# RC_simple.net
KiCad netlist of a schematic drawn in EAGLE
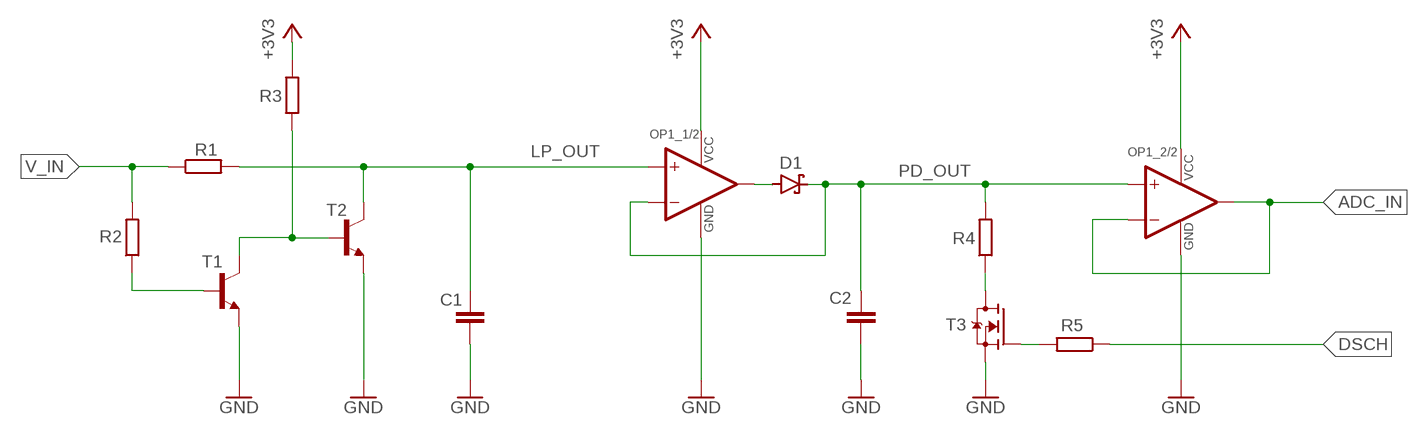
[diagram p0: schematic, sheet 1]

(export (version "E")
  (design (tool "Eeschema 10.0.6"))
  (components
    (comp (ref "C1")
      (value "CAP_CERAMIC_0603")
      (footprint "eagle-import:SMD_0603C")
      (libsource (lib "eagle-import") (part "CAP_CERAMIC_0603"))
    )
    (comp (ref "C2")
      (value "CAP_CERAMIC_0603")
      (footprint "eagle-import:SMD_0603C")
      (libsource (lib "eagle-import") (part "CAP_CERAMIC_0603"))
    )
    (comp (ref "D1")
      (value "BAT54")
      (footprint "eagle-import:SOT23")
      (libsource (lib "eagle-import") (part "BAT54"))
    )
    (comp (ref "OP1")
      (value "MAX_OP_AMPUMAX")
      (footprint "eagle-import:SOT23-8")
      (libsource (lib "eagle-import") (part "MAX_OP_AMPUMAX"))
    )
    (comp (ref "OP2")
      (value "MAX_OP_AMPUMAX")
      (footprint "eagle-import:SOT23-8")
      (libsource (lib "eagle-import") (part "MAX_OP_AMPUMAX"))
    )
    (comp (ref "R1")
      (value "RESISTOR_0603")
      (footprint "eagle-import:SMD_0603")
      (libsource (lib "eagle-import") (part "RESISTOR_0603"))
    )
    (comp (ref "R2")
      (value "RESISTOR_0603")
      (footprint "eagle-import:SMD_0603")
      (libsource (lib "eagle-import") (part "RESISTOR_0603"))
    )
    (comp (ref "R3")
      (value "RESISTOR_0603")
      (footprint "eagle-import:SMD_0603")
      (libsource (lib "eagle-import") (part "RESISTOR_0603"))
    )
    (comp (ref "R4")
      (value "RESISTOR_0603")
      (footprint "eagle-import:SMD_0603")
      (libsource (lib "eagle-import") (part "RESISTOR_0603"))
    )
    (comp (ref "R5")
      (value "RESISTOR_0603")
      (footprint "eagle-import:SMD_0603")
      (libsource (lib "eagle-import") (part "RESISTOR_0603"))
    )
    (comp (ref "T1")
      (value "BC847")
      (footprint "eagle-import:SOT23")
      (libsource (lib "eagle-import") (part "BC847"))
    )
    (comp (ref "T2")
      (value "BC847")
      (footprint "eagle-import:SOT23")
      (libsource (lib "eagle-import") (part "BC847"))
    )
    (comp (ref "T3")
      (value "BSS138")
      (footprint "eagle-import:SOT-23-3")
      (libsource (lib "eagle-import") (part "BSS138"))
    )
  )
  (nets
    (net (code "1") (name "+3V3") (class "Default")
      (node (ref "OP1") (pin "P$8") (pinfunction "V+_P$8") (pintype "power_in"))
      (node (ref "OP2") (pin "P$8") (pinfunction "V+_P$8") (pintype "power_in"))
      (node (ref "R3") (pin "2") (pinfunction "2_2") (pintype "passive"))
    )
    (net (code "2") (name "/LP_OUT") (class "Default")
      (node (ref "C1") (pin "1") (pinfunction "1_1") (pintype "passive"))
      (node (ref "OP1") (pin "P$3") (pinfunction "+IN_P$3") (pintype "input"))
      (node (ref "R1") (pin "2") (pinfunction "2_2") (pintype "passive"))
      (node (ref "T2") (pin "3") (pinfunction "C_3") (pintype "passive"))
    )
    (net (code "3") (name "/PD_OUT") (class "Default")
      (node (ref "C2") (pin "1") (pinfunction "1_1") (pintype "passive"))
      (node (ref "D1") (pin "3") (pinfunction "C_3") (pintype "passive"))
      (node (ref "OP1") (pin "P$2") (pinfunction "-IN_P$2") (pintype "input"))
      (node (ref "OP1") (pin "P$5") (pinfunction "+IN_P$5") (pintype "input"))
      (node (ref "R4") (pin "2") (pinfunction "2_2") (pintype "passive"))
    )
    (net (code "4") (name "ADC_IN") (class "Default")
      (node (ref "OP1") (pin "P$6") (pinfunction "-IN_P$6") (pintype "input"))
      (node (ref "OP1") (pin "P$7") (pinfunction "OUT_P$7") (pintype "output"))
    )
    (net (code "5") (name "DSCH") (class "Default")
      (node (ref "R5") (pin "1") (pinfunction "1_1") (pintype "passive"))
    )
    (net (code "6") (name "GND") (class "Default")
      (node (ref "C1") (pin "2") (pinfunction "2_2") (pintype "passive"))
      (node (ref "C2") (pin "2") (pinfunction "2_2") (pintype "passive"))
      (node (ref "OP1") (pin "P$4") (pinfunction "V-_P$4") (pintype "power_in"))
      (node (ref "OP2") (pin "P$4") (pinfunction "V-_P$4") (pintype "power_in"))
      (node (ref "T1") (pin "2") (pinfunction "E_2") (pintype "passive"))
      (node (ref "T2") (pin "2") (pinfunction "E_2") (pintype "passive"))
      (node (ref "T3") (pin "2") (pinfunction "S_2") (pintype "bidirectional"))
    )
    (net (code "7") (name "Net-(D1-A)") (class "Default")
      (node (ref "D1") (pin "1") (pinfunction "A_1") (pintype "passive"))
      (node (ref "OP1") (pin "P$1") (pinfunction "OUT_P$1") (pintype "output"))
    )
    (net (code "8") (name "Net-(T1-B)") (class "Default")
      (node (ref "R2") (pin "1") (pinfunction "1_1") (pintype "passive"))
      (node (ref "T1") (pin "1") (pinfunction "B_1") (pintype "passive"))
    )
    (net (code "9") (name "Net-(T1-C)") (class "Default")
      (node (ref "R3") (pin "1") (pinfunction "1_1") (pintype "passive"))
      (node (ref "T1") (pin "3") (pinfunction "C_3") (pintype "passive"))
      (node (ref "T2") (pin "1") (pinfunction "B_1") (pintype "passive"))
    )
    (net (code "10") (name "Net-(T3-D)") (class "Default")
      (node (ref "R4") (pin "1") (pinfunction "1_1") (pintype "passive"))
      (node (ref "T3") (pin "3") (pinfunction "D_3") (pintype "bidirectional"))
    )
    (net (code "11") (name "Net-(T3-G)") (class "Default")
      (node (ref "R5") (pin "2") (pinfunction "2_2") (pintype "passive"))
      (node (ref "T3") (pin "1") (pinfunction "G_1") (pintype "bidirectional"))
    )
    (net (code "12") (name "V_IN") (class "Default")
      (node (ref "R1") (pin "1") (pinfunction "1_1") (pintype "passive"))
      (node (ref "R2") (pin "2") (pinfunction "2_2") (pintype "passive"))
    )
  )
)
